# 5_USB-UART.net
KiCad netlist of a schematic drawn in Altium Designer
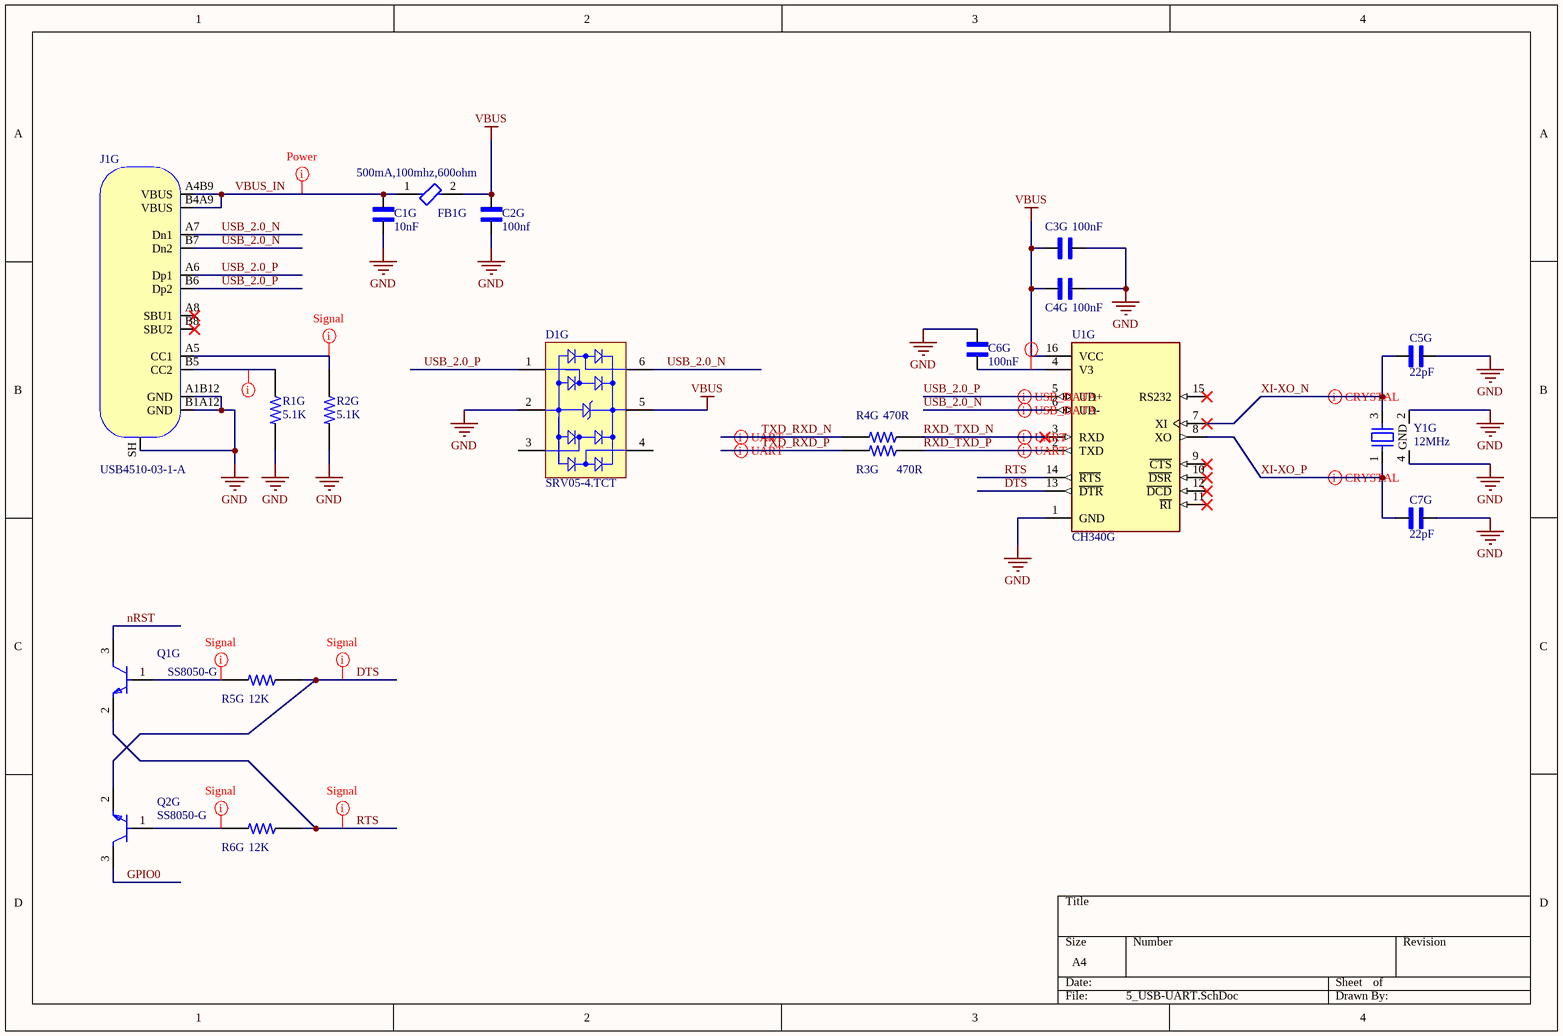
[diagram p0: 5_USB-UART.SchDoc]

(export (version "E")
  (design (tool "Eeschema 10.0.6"))
  (components
    (comp (ref "C1G")
      (value "10nF")
      (footprint "C-0603")
      (description "Ceramic Capacitor 16V 0603 (1608 Metric)")
      (fields (field (name "MP") "C0603C104J4RAC") (field (name "MF") "KEMET"))
      (libsource (lib "") (part "C-0603_2"))
    )
    (comp (ref "C2G")
      (value "100nf")
      (footprint "C-0603")
      (description "Ceramic Capacitor 16V 0603 (1608 Metric)")
      (fields (field (name "MP") "C0603C104J4RAC") (field (name "MF") "KEMET"))
      (libsource (lib "") (part "C-0603_2"))
    )
    (comp (ref "C3G")
      (value "100nF")
      (footprint "C-0603")
      (description "Ceramic Capacitor 16V 0603 (1608 Metric)")
      (fields (field (name "MP") "C0603C104J4RAC") (field (name "MF") "KEMET"))
      (libsource (lib "") (part "C-0603_3"))
    )
    (comp (ref "C4G")
      (value "100nF")
      (footprint "C-0603")
      (description "Ceramic Capacitor 16V 0603 (1608 Metric)")
      (fields (field (name "MP") "C0603C104J4RAC") (field (name "MF") "KEMET"))
      (libsource (lib "") (part "C-0603_3"))
    )
    (comp (ref "C5G")
      (value "22pF")
      (footprint "C-0603")
      (description "Ceramic Capacitor 16V 0603 (1608 Metric)")
      (fields (field (name "MP") "C0603C104J4RAC") (field (name "MF") "KEMET"))
      (libsource (lib "") (part "C-0603_1"))
    )
    (comp (ref "C6G")
      (value "100nF")
      (footprint "C-0603")
      (description "Ceramic Capacitor 16V 0603 (1608 Metric)")
      (fields (field (name "MP") "C0603C104J4RAC") (field (name "MF") "KEMET"))
      (libsource (lib "ESP-12F_WLED_IOT_LIPO") (part "C-0603"))
    )
    (comp (ref "C7G")
      (value "22pF")
      (footprint "C-0603")
      (description "Ceramic Capacitor 16V 0603 (1608 Metric)")
      (fields (field (name "MP") "C0603C104J4RAC") (field (name "MF") "KEMET"))
      (libsource (lib "") (part "C-0603_1"))
    )
    (comp (ref "D1G")
      (value "SRV05-4.TCT")
      (footprint "SMTC-SOT23-6_V")
      (fields (field (name "MANUFACTURER") "Semtech"))
      (libsource (lib "ESP-12F_WLED_IOT_LIPO") (part "STM-USB_DVI_HDMIULC6-4SC6X-SOT23-6L"))
    )
    (comp (ref "FB1G")
      (value "500mA,100mhz,600ohm")
      (footprint "FP-BLM21-0_2-t0_85-e0_5-IPC_A")
      (description "BLM21BB121SN1D")
      (fields (field (name "TOLERANCE") "25%"))
      (libsource (lib "ESP-12F_WLED_IOT_LIPO") (part "5f30dd21d616792df468990f7003faa"))
    )
    (comp (ref "J1G")
      (value "USB4510-03-1-A")
      (footprint "USB4510-03-1-A")
      (description "USB Connector Type C SMT Mid-Mount 16 Pin")
      (fields (field (name "MANUFACTURER") "GCT"))
      (libsource (lib "ESP-12F_WLED_IOT_LIPO") (part "USB4510-03-1-A"))
    )
    (comp (ref "Q1G")
      (value "SS8050-G")
      (footprint "FP-SS8050-G-MFG")
      (description "NPN TRANSISTOR 1.5A 40V SOT-23 R")
      (libsource (lib "ESP-12F_WLED_IOT_LIPO") (part "2a1388f82443b098dcd57d24ac7632d"))
    )
    (comp (ref "Q2G")
      (value "SS8050-G")
      (footprint "FP-SS8050-G-MFG")
      (description "NPN TRANSISTOR 1.5A 40V SOT-23 R")
      (libsource (lib "ESP-12F_WLED_IOT_LIPO") (part "2a1388f82443b098dcd57d24ac7632d"))
    )
    (comp (ref "R1G")
      (value "5.1K")
      (footprint "R-0603")
      (description "0603")
      (fields (field (name "MP") "2-1623703-0") (field (name "TOLERANCE") "1%"))
      (libsource (lib "ESP-12F_WLED_IOT_LIPO") (part "R-0603"))
    )
    (comp (ref "R2G")
      (value "5.1K")
      (footprint "R-0603")
      (description "0603")
      (fields (field (name "MP") "2-1623703-0") (field (name "TOLERANCE") "1%"))
      (libsource (lib "ESP-12F_WLED_IOT_LIPO") (part "R-0603"))
    )
    (comp (ref "R3G")
      (value "470R")
      (footprint "R-0603")
      (description "0603")
      (fields (field (name "MP") "2-1623703-0") (field (name "TOLERANCE") "1%"))
      (libsource (lib "ESP-12F_WLED_IOT_LIPO") (part "R-0603"))
    )
    (comp (ref "R4G")
      (value "470R")
      (footprint "R-0603")
      (description "0603")
      (fields (field (name "MP") "2-1623703-0") (field (name "TOLERANCE") "1%"))
      (libsource (lib "ESP-12F_WLED_IOT_LIPO") (part "R-0603"))
    )
    (comp (ref "R5G")
      (value "12K")
      (footprint "R-0603")
      (description "0603")
      (fields (field (name "MP") "2-1623703-0") (field (name "TOLERANCE") "1%"))
      (libsource (lib "ESP-12F_WLED_IOT_LIPO") (part "R-0603"))
    )
    (comp (ref "R6G")
      (value "12K")
      (footprint "R-0603")
      (description "0603")
      (fields (field (name "MP") "2-1623703-0") (field (name "TOLERANCE") "1%"))
      (libsource (lib "ESP-12F_WLED_IOT_LIPO") (part "R-0603"))
    )
    (comp (ref "U1G")
      (value "CH340G")
      (footprint "SOIC127P600X180-16N")
      (libsource (lib "ESP-12F_WLED_IOT_LIPO") (part "CH340G"))
    )
    (comp (ref "Y1G")
      (value "12MHz")
      (footprint "ABRACON ABM10")
      (description "CRYSTAL 12.00MHZ 8PF LOW ESR SMD")
      (fields
        (field (name "PART NUMBER") "ABM10-167-12.000MHZ-T3")
        (field (name "MANUFACTURER") "Abracon LLC")
      )
      (libsource (lib "ESP-12F_WLED_IOT_LIPO") (part "Abracon Crystal ABM10"))
    )
  )
  (nets
    (net (code "1") (name "/DTS") (class "Default")
      (node (ref "Q2G") (pin "2") (pinfunction "E_2") (pintype "passive"))
      (node (ref "R5G") (pin "1") (pinfunction "1_1") (pintype "passive"))
      (node (ref "U1G") (pin "13") (pinfunction "~{DTR}_13") (pintype "output"))
    )
    (net (code "2") (name "/GPIO0") (class "Default")
      (node (ref "Q2G") (pin "3") (pinfunction "C_3") (pintype "passive"))
    )
    (net (code "3") (name "/RTS") (class "Default")
      (node (ref "Q1G") (pin "2") (pinfunction "E_2") (pintype "passive"))
      (node (ref "R6G") (pin "1") (pinfunction "1_1") (pintype "passive"))
      (node (ref "U1G") (pin "14") (pinfunction "~{RTS}_14") (pintype "output"))
    )
    (net (code "4") (name "/RXD_TXD_N") (class "Default")
      (node (ref "R3G") (pin "1") (pinfunction "1_1") (pintype "passive"))
      (node (ref "U1G") (pin "3") (pinfunction "RXD_3") (pintype "input"))
    )
    (net (code "5") (name "/RXD_TXD_P") (class "Default")
      (node (ref "R4G") (pin "1") (pinfunction "1_1") (pintype "passive"))
      (node (ref "U1G") (pin "2") (pinfunction "TXD_2") (pintype "output"))
    )
    (net (code "6") (name "/TXD_RXD_N") (class "Default")
      (node (ref "R3G") (pin "2") (pinfunction "2_2") (pintype "passive"))
    )
    (net (code "7") (name "/TXD_RXD_P") (class "Default")
      (node (ref "R4G") (pin "2") (pinfunction "2_2") (pintype "passive"))
    )
    (net (code "8") (name "/USB_2.0_N") (class "Default")
      (node (ref "D1G") (pin "6") (pinfunction "I/O_4_6") (pintype "passive"))
      (node (ref "J1G") (pin "A7") (pinfunction "Dn1_A7") (pintype "passive"))
      (node (ref "J1G") (pin "B7") (pinfunction "Dn2_B7") (pintype "passive"))
      (node (ref "U1G") (pin "6") (pinfunction "UD-_6") (pintype "bidirectional"))
    )
    (net (code "9") (name "/USB_2.0_P") (class "Default")
      (node (ref "D1G") (pin "1") (pinfunction "I/O_1_1") (pintype "passive"))
      (node (ref "J1G") (pin "A6") (pinfunction "Dp1_A6") (pintype "passive"))
      (node (ref "J1G") (pin "B6") (pinfunction "Dp2_B6") (pintype "passive"))
      (node (ref "U1G") (pin "5") (pinfunction "UD+_5") (pintype "bidirectional"))
    )
    (net (code "10") (name "/VBUS_IN") (class "Default")
      (node (ref "C1G") (pin "2") (pinfunction "2_2") (pintype "passive"))
      (node (ref "FB1G") (pin "1") (pinfunction "1_1") (pintype "passive"))
      (node (ref "J1G") (pin "A4B9") (pinfunction "VBUS_A4B9") (pintype "passive"))
      (node (ref "J1G") (pin "B4A9") (pinfunction "VBUS_B4A9") (pintype "passive"))
    )
    (net (code "11") (name "/XI-XO_N") (class "Default")
      (node (ref "C5G") (pin "1") (pinfunction "1_1") (pintype "passive"))
      (node (ref "U1G") (pin "7") (pinfunction "XI_7") (pintype "input"))
      (node (ref "Y1G") (pin "3") (pinfunction "3_3") (pintype "passive"))
    )
    (net (code "12") (name "/XI-XO_P") (class "Default")
      (node (ref "C7G") (pin "1") (pinfunction "1_1") (pintype "passive"))
      (node (ref "U1G") (pin "8") (pinfunction "XO_8") (pintype "output"))
      (node (ref "Y1G") (pin "1") (pinfunction "1_1") (pintype "passive"))
    )
    (net (code "13") (name "/nRST") (class "Default")
      (node (ref "Q1G") (pin "3") (pinfunction "C_3") (pintype "passive"))
    )
    (net (code "14") (name "GND") (class "Default")
      (node (ref "C1G") (pin "1") (pinfunction "1_1") (pintype "passive"))
      (node (ref "C2G") (pin "1") (pinfunction "1_1") (pintype "passive"))
      (node (ref "C3G") (pin "1") (pinfunction "1_1") (pintype "passive"))
      (node (ref "C4G") (pin "1") (pinfunction "1_1") (pintype "passive"))
      (node (ref "C5G") (pin "2") (pinfunction "2_2") (pintype "passive"))
      (node (ref "C6G") (pin "1") (pinfunction "1_1") (pintype "passive"))
      (node (ref "C7G") (pin "2") (pinfunction "2_2") (pintype "passive"))
      (node (ref "D1G") (pin "2") (pinfunction "GND_2") (pintype "passive"))
      (node (ref "J1G") (pin "A1B12") (pinfunction "GND_A1B12") (pintype "passive"))
      (node (ref "J1G") (pin "B1A12") (pinfunction "GND_B1A12") (pintype "passive"))
      (node (ref "J1G") (pin "SH") (pinfunction "SHIELD_SH") (pintype "passive"))
      (node (ref "R1G") (pin "2") (pinfunction "2_2") (pintype "passive"))
      (node (ref "R2G") (pin "2") (pinfunction "2_2") (pintype "passive"))
      (node (ref "U1G") (pin "1") (pinfunction "GND_1") (pintype "power_in"))
      (node (ref "Y1G") (pin "2") (pinfunction "GND_2") (pintype "passive"))
      (node (ref "Y1G") (pin "4") (pinfunction "GND_4") (pintype "passive"))
    )
    (net (code "15") (name "Net-(J1G-CC1)") (class "Default")
      (node (ref "J1G") (pin "A5") (pinfunction "CC1_A5") (pintype "passive"))
      (node (ref "R2G") (pin "1") (pinfunction "1_1") (pintype "passive"))
    )
    (net (code "16") (name "Net-(J1G-CC2)") (class "Default")
      (node (ref "J1G") (pin "B5") (pinfunction "CC2_B5") (pintype "passive"))
      (node (ref "R1G") (pin "1") (pinfunction "1_1") (pintype "passive"))
    )
    (net (code "17") (name "Net-(Q1G-B)") (class "Default")
      (node (ref "Q1G") (pin "1") (pinfunction "B_1") (pintype "passive"))
      (node (ref "R5G") (pin "2") (pinfunction "2_2") (pintype "passive"))
    )
    (net (code "18") (name "Net-(Q2G-B)") (class "Default")
      (node (ref "Q2G") (pin "1") (pinfunction "B_1") (pintype "passive"))
      (node (ref "R6G") (pin "2") (pinfunction "2_2") (pintype "passive"))
    )
    (net (code "19") (name "Net-(U1G-V3)") (class "Default")
      (node (ref "C6G") (pin "2") (pinfunction "2_2") (pintype "passive"))
      (node (ref "U1G") (pin "4") (pinfunction "V3_4") (pintype "power_in"))
    )
    (net (code "20") (name "VBUS") (class "Default")
      (node (ref "C2G") (pin "2") (pinfunction "2_2") (pintype "passive"))
      (node (ref "C3G") (pin "2") (pinfunction "2_2") (pintype "passive"))
      (node (ref "C4G") (pin "2") (pinfunction "2_2") (pintype "passive"))
      (node (ref "D1G") (pin "5") (pinfunction "VBUS_5") (pintype "passive"))
      (node (ref "FB1G") (pin "2") (pinfunction "2_2") (pintype "passive"))
      (node (ref "U1G") (pin "16") (pinfunction "VCC_16") (pintype "power_in"))
    )
    (net (code "21") (name "unconnected-(D1G-I{slash}O_2-Pad3)") (class "Default")
      (node (ref "D1G") (pin "3") (pinfunction "I/O_2_3") (pintype "passive"))
    )
    (net (code "22") (name "unconnected-(D1G-I{slash}O_3-Pad4)") (class "Default")
      (node (ref "D1G") (pin "4") (pinfunction "I/O_3_4") (pintype "passive"))
    )
    (net (code "23") (name "unconnected-(J1G-SBU1-PadA8)") (class "Default")
      (node (ref "J1G") (pin "A8") (pinfunction "SBU1_A8") (pintype "passive+no_connect"))
    )
    (net (code "24") (name "unconnected-(J1G-SBU2-PadB8)") (class "Default")
      (node (ref "J1G") (pin "B8") (pinfunction "SBU2_B8") (pintype "passive+no_connect"))
    )
    (net (code "25") (name "unconnected-(U1G-RS232-Pad15)") (class "Default")
      (node (ref "U1G") (pin "15") (pinfunction "RS232_15") (pintype "input+no_connect"))
    )
    (net (code "26") (name "unconnected-(U1G-~{CTS}-Pad9)") (class "Default")
      (node (ref "U1G") (pin "9") (pinfunction "~{CTS}_9") (pintype "input+no_connect"))
    )
    (net (code "27") (name "unconnected-(U1G-~{DCD}-Pad12)") (class "Default")
      (node (ref "U1G") (pin "12") (pinfunction "~{DCD}_12") (pintype "input+no_connect"))
    )
    (net (code "28") (name "unconnected-(U1G-~{DSR}-Pad10)") (class "Default")
      (node (ref "U1G") (pin "10") (pinfunction "~{DSR}_10") (pintype "input+no_connect"))
    )
    (net (code "29") (name "unconnected-(U1G-~{RI}-Pad11)") (class "Default")
      (node (ref "U1G") (pin "11") (pinfunction "~{RI}_11") (pintype "input+no_connect"))
    )
  )
)
